# schematic.net
KiCad netlist of a schematic drawn in EasyEDA
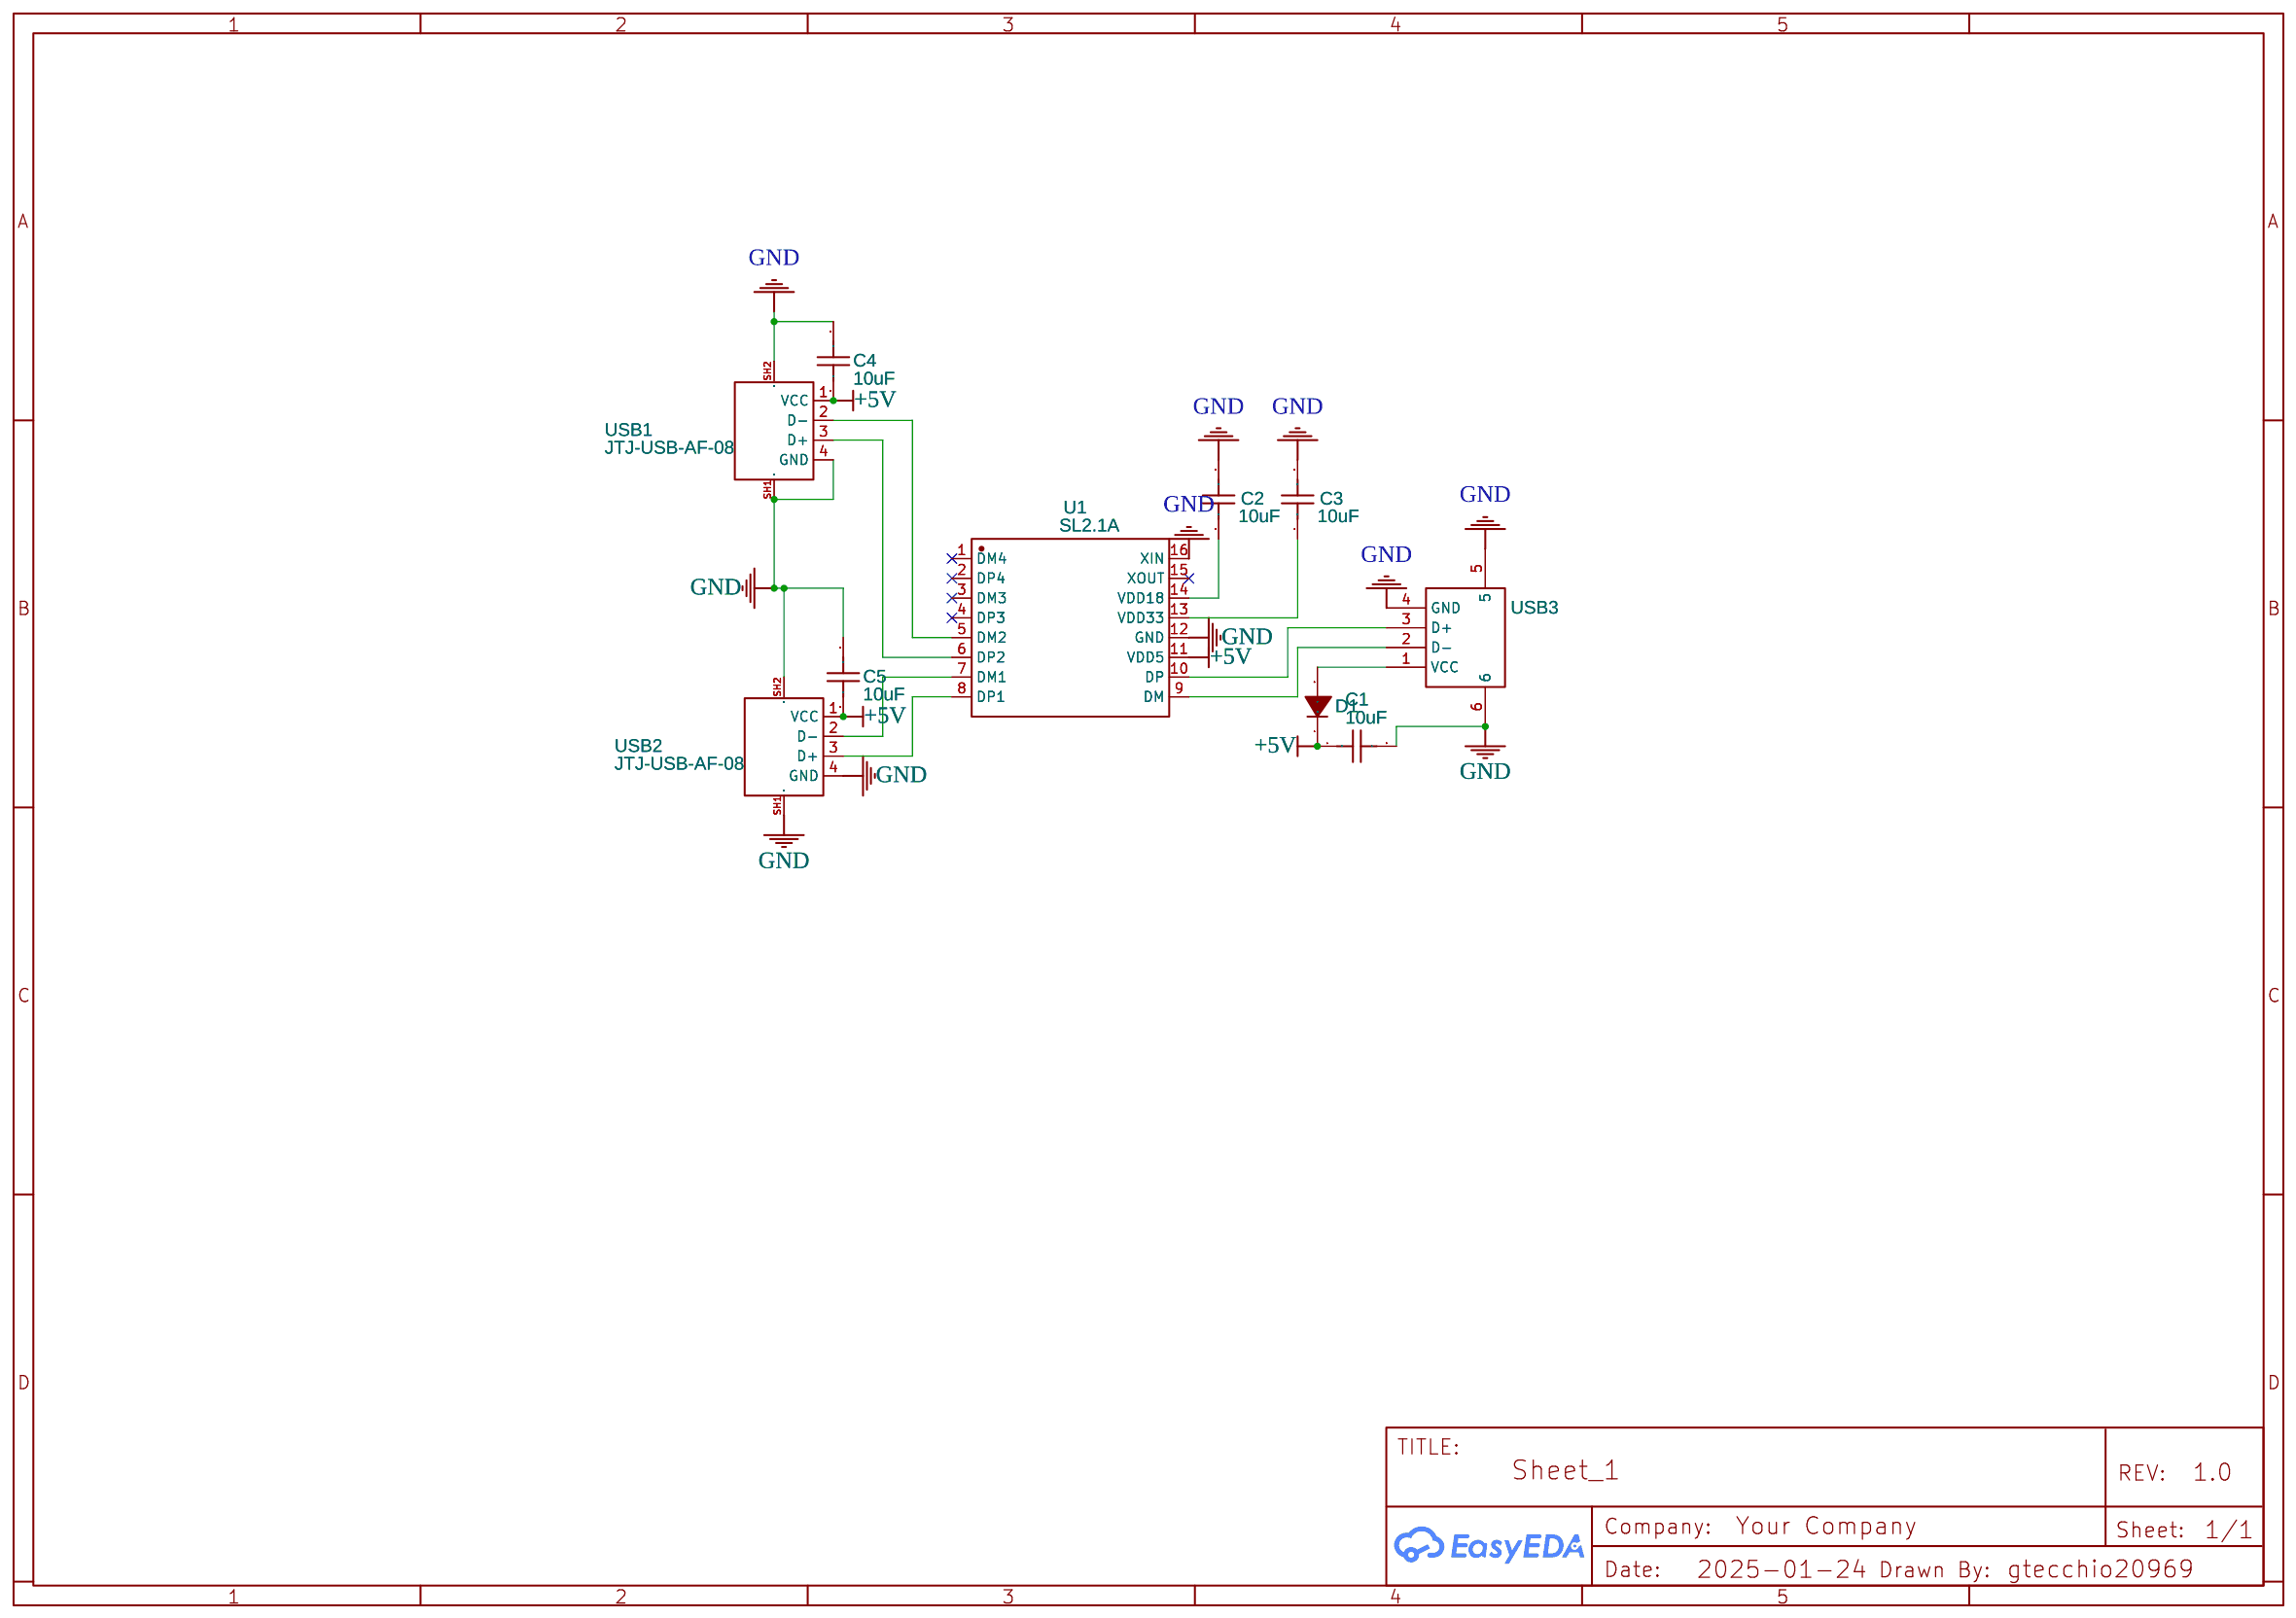
[diagram p0: schematic sheet]

(export (version "E")
  (design (tool "Eeschema 10.0.6"))
  (components
    (comp (ref "C1")
      (value "10uF")
      (fields
        (field (name "Manufacturer Part") "CL10A106KP8NNNC")
        (field (name "Manufacturer") "SAMSUNG(三星)")
      )
      (libsource (lib "") (part "CL10A106KP8NNNC_1"))
    )
    (comp (ref "C2")
      (value "10uF")
      (fields
        (field (name "Manufacturer Part") "CL10A106KP8NNNC")
        (field (name "Manufacturer") "SAMSUNG(三星)")
      )
      (libsource (lib "") (part "CL10A106KP8NNNC"))
    )
    (comp (ref "C3")
      (value "10uF")
      (fields
        (field (name "Manufacturer Part") "CL10A106KP8NNNC")
        (field (name "Manufacturer") "SAMSUNG(三星)")
      )
      (libsource (lib "") (part "CL10A106KP8NNNC"))
    )
    (comp (ref "C4")
      (value "10uF")
      (fields
        (field (name "Manufacturer Part") "CL10A106KP8NNNC")
        (field (name "Manufacturer") "SAMSUNG(三星)")
      )
      (libsource (lib "") (part "CL10A106KP8NNNC"))
    )
    (comp (ref "C5")
      (value "10uF")
      (fields
        (field (name "Manufacturer Part") "CL10A106KP8NNNC")
        (field (name "Manufacturer") "SAMSUNG(三星)")
      )
      (libsource (lib "") (part "CL10A106KP8NNNC_2"))
    )
    (comp (ref "D1")
      (value "NSR0320MW2T1G")
      (fields (field (name "Manufacturer") "onsemi(安森美)"))
      (libsource (lib "") (part "NSR0320MW2T1G"))
    )
    (comp (ref "U1")
      (value "SL2.1A")
      (fields (field (name "Manufacturer") "CoreChips(和芯润德)"))
      (libsource (lib "") (part "SL2.1A"))
    )
    (comp (ref "USB1")
      (value "JTJ-USB-AF-08")
      (fields (field (name "Manufacturer Part") "902-131A1011D10100") (field (name "Manufacturer") "精拓金"))
      (libsource (lib "") (part "JTJ-USB-AF-08"))
    )
    (comp (ref "USB2")
      (value "JTJ-USB-AF-08")
      (fields (field (name "Manufacturer Part") "902-131A1011D10100") (field (name "Manufacturer") "精拓金"))
      (libsource (lib "") (part "JTJ-USB-AF-08"))
    )
    (comp (ref "USB3")
      (value "U-G-04DD-W-01")
      (fields (field (name "Manufacturer Part") "U-G-O4DD-W-1") (field (name "Manufacturer") "韩国韩荣"))
      (libsource (lib "") (part "U-G-04DD-W-01"))
    )
  )
  (nets
    (net (code "1") (name "+5V") (class "Default")
      (node (ref "C1") (pin "1") (pinfunction "1_1") (pintype "unspecified"))
      (node (ref "C4") (pin "1") (pinfunction "1_1") (pintype "unspecified"))
      (node (ref "C5") (pin "2") (pinfunction "2_2") (pintype "unspecified"))
      (node (ref "D1") (pin "1") (pinfunction "C_1") (pintype "unspecified"))
      (node (ref "U1") (pin "11") (pinfunction "VDD5_11") (pintype "unspecified"))
      (node (ref "USB1") (pin "1") (pinfunction "VCC_1") (pintype "input"))
      (node (ref "USB2") (pin "1") (pinfunction "VCC_1") (pintype "input"))
    )
    (net (code "2") (name "GND") (class "Default")
      (node (ref "C1") (pin "2") (pinfunction "2_2") (pintype "unspecified"))
      (node (ref "C2") (pin "2") (pinfunction "2_2") (pintype "unspecified"))
      (node (ref "C3") (pin "2") (pinfunction "2_2") (pintype "unspecified"))
      (node (ref "C4") (pin "2") (pinfunction "2_2") (pintype "unspecified"))
      (node (ref "C5") (pin "1") (pinfunction "1_1") (pintype "unspecified"))
      (node (ref "U1") (pin "12") (pinfunction "GND_12") (pintype "unspecified"))
      (node (ref "U1") (pin "16") (pinfunction "XIN_16") (pintype "unspecified"))
      (node (ref "USB1") (pin "4") (pinfunction "GND_4") (pintype "input"))
      (node (ref "USB1") (pin "SH1") (pinfunction "SH1_SH1") (pintype "unspecified"))
      (node (ref "USB1") (pin "SH2") (pinfunction "SH2_SH2") (pintype "unspecified"))
      (node (ref "USB2") (pin "4") (pinfunction "GND_4") (pintype "input"))
      (node (ref "USB2") (pin "SH1") (pinfunction "SH1_SH1") (pintype "unspecified"))
      (node (ref "USB2") (pin "SH2") (pinfunction "SH2_SH2") (pintype "unspecified"))
      (node (ref "USB3") (pin "4") (pinfunction "GND_4") (pintype "unspecified"))
      (node (ref "USB3") (pin "5") (pinfunction "5_5") (pintype "unspecified"))
      (node (ref "USB3") (pin "6") (pinfunction "6_6") (pintype "unspecified"))
    )
    (net (code "3") (name "Net-(D1-A)") (class "Default")
      (node (ref "D1") (pin "2") (pinfunction "A_2") (pintype "unspecified"))
      (node (ref "USB3") (pin "1") (pinfunction "VCC_1") (pintype "unspecified"))
    )
    (net (code "4") (name "Net-(U1-DM)") (class "Default")
      (node (ref "U1") (pin "9") (pinfunction "DM_9") (pintype "unspecified"))
      (node (ref "USB3") (pin "2") (pinfunction "D-_2") (pintype "unspecified"))
    )
    (net (code "5") (name "Net-(U1-DM1)") (class "Default")
      (node (ref "U1") (pin "7") (pinfunction "DM1_7") (pintype "unspecified"))
      (node (ref "USB2") (pin "2") (pinfunction "D-_2") (pintype "input"))
    )
    (net (code "6") (name "Net-(U1-DM2)") (class "Default")
      (node (ref "U1") (pin "5") (pinfunction "DM2_5") (pintype "unspecified"))
      (node (ref "USB1") (pin "2") (pinfunction "D-_2") (pintype "input"))
    )
    (net (code "7") (name "Net-(U1-DP)") (class "Default")
      (node (ref "U1") (pin "10") (pinfunction "DP_10") (pintype "unspecified"))
      (node (ref "USB3") (pin "3") (pinfunction "D+_3") (pintype "unspecified"))
    )
    (net (code "8") (name "Net-(U1-DP1)") (class "Default")
      (node (ref "U1") (pin "8") (pinfunction "DP1_8") (pintype "unspecified"))
      (node (ref "USB2") (pin "3") (pinfunction "D+_3") (pintype "input"))
    )
    (net (code "9") (name "Net-(U1-DP2)") (class "Default")
      (node (ref "U1") (pin "6") (pinfunction "DP2_6") (pintype "unspecified"))
      (node (ref "USB1") (pin "3") (pinfunction "D+_3") (pintype "input"))
    )
    (net (code "10") (name "Net-(U1-VDD18)") (class "Default")
      (node (ref "C2") (pin "1") (pinfunction "1_1") (pintype "unspecified"))
      (node (ref "U1") (pin "14") (pinfunction "VDD18_14") (pintype "unspecified"))
    )
    (net (code "11") (name "Net-(U1-VDD33)") (class "Default")
      (node (ref "C3") (pin "1") (pinfunction "1_1") (pintype "unspecified"))
      (node (ref "U1") (pin "13") (pinfunction "VDD33_13") (pintype "unspecified"))
    )
    (net (code "12") (name "unconnected-(U1-DM3-Pad3)") (class "Default")
      (node (ref "U1") (pin "3") (pinfunction "DM3_3") (pintype "unspecified+no_connect"))
    )
    (net (code "13") (name "unconnected-(U1-DM4-Pad1)") (class "Default")
      (node (ref "U1") (pin "1") (pinfunction "DM4_1") (pintype "unspecified+no_connect"))
    )
    (net (code "14") (name "unconnected-(U1-DP3-Pad4)") (class "Default")
      (node (ref "U1") (pin "4") (pinfunction "DP3_4") (pintype "unspecified+no_connect"))
    )
    (net (code "15") (name "unconnected-(U1-DP4-Pad2)") (class "Default")
      (node (ref "U1") (pin "2") (pinfunction "DP4_2") (pintype "unspecified+no_connect"))
    )
    (net (code "16") (name "unconnected-(U1-XOUT-Pad15)") (class "Default")
      (node (ref "U1") (pin "15") (pinfunction "XOUT_15") (pintype "unspecified+no_connect"))
    )
  )
)
